# var_9.net
KiCad netlist of a schematic drawn in Altium Designer
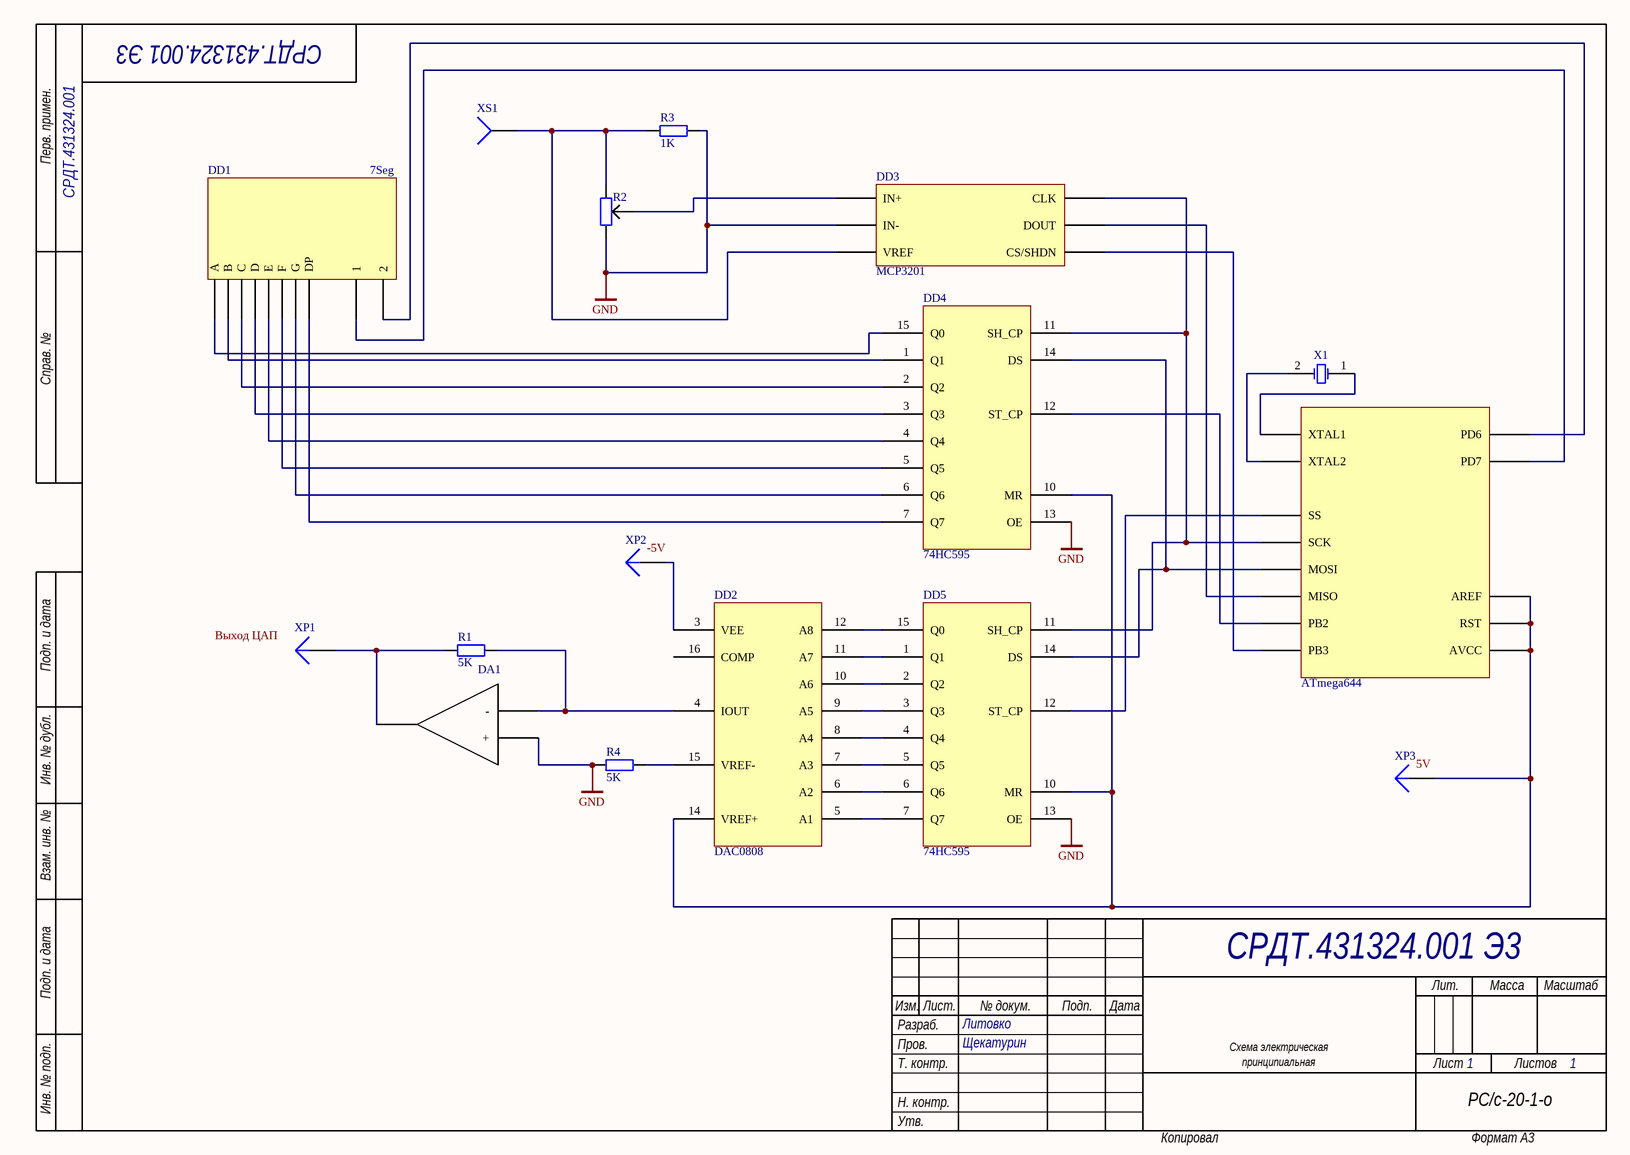
[diagram p0: var 9.SchDoc]

(export (version "E")
  (design (tool "Eeschema 10.0.6"))
  (components
    (comp (ref "*") (value "Potentiometr") (libsource (lib "lib") (part "Potentiometr")))
    (comp (ref "ATmega644") (value "mcu") (libsource (lib "lib") (part "mcu")))
    (comp (ref "DA1") (value "OP1P") (libsource (lib "lib") (part "OP1P")))
    (comp (ref "DD1") (value "7Seg") (libsource (lib "lib") (part "7Seg")))
    (comp (ref "DD2") (value "DAC0808") (libsource (lib "lib") (part "DAC0808")))
    (comp (ref "DD3") (value "MCP3201") (libsource (lib "lib") (part "MCP3201")))
    (comp (ref "DD4") (value "74HC595") (libsource (lib "lib") (part "74HC595")))
    (comp (ref "DD5") (value "74HC595") (libsource (lib "lib") (part "74HC595")))
    (comp (ref "R1")
      (value "5K")
      (footprint "AXIAL-0.4")
      (description "Resistor")
      (fields (field (name "Comment") "Res2") (field (name "PUBLISHER") "Altium Limited"))
      (libsource (lib "") (part "Res2_1"))
    )
    (comp (ref "R2")
      (value "Res2")
      (footprint "AXIAL-0.4")
      (description "Resistor")
      (fields (field (name "PUBLISHER") "Altium Limited"))
      (libsource (lib "Miscellaneous Devices") (part "Res2"))
    )
    (comp (ref "R3")
      (value "1K")
      (footprint "AXIAL-0.4")
      (description "Resistor")
      (fields (field (name "Comment") "Res2") (field (name "PUBLISHER") "Altium Limited"))
      (libsource (lib "") (part "Res2_1"))
    )
    (comp (ref "R4")
      (value "5K")
      (footprint "AXIAL-0.4")
      (description "Resistor")
      (fields (field (name "Comment") "Res2") (field (name "PUBLISHER") "Altium Limited"))
      (libsource (lib "") (part "Res2_1"))
    )
    (comp (ref "X1")
      (value "XTAL")
      (footprint "R38")
      (description "Crystal Oscillator")
      (fields (field (name "PUBLISHER") "Altium Limited"))
      (libsource (lib "Miscellaneous Devices") (part "XTAL"))
    )
    (comp (ref "XP1")
      (value "Plug")
      (footprint "PIN1")
      (fields (field (name "PUBLISHER") "Altium Limited"))
      (libsource (lib "Miscellaneous Connectors") (part "Plug"))
    )
    (comp (ref "XP2")
      (value "Plug")
      (footprint "PIN1")
      (fields (field (name "PUBLISHER") "Altium Limited"))
      (libsource (lib "Miscellaneous Connectors") (part "Plug"))
    )
    (comp (ref "XP3")
      (value "Plug")
      (footprint "PIN1")
      (fields (field (name "PUBLISHER") "Altium Limited"))
      (libsource (lib "Miscellaneous Connectors") (part "Plug"))
    )
    (comp (ref "XS1")
      (value "Socket")
      (footprint "PIN1")
      (fields (field (name "PUBLISHER") "Altium Limited"))
      (libsource (lib "Miscellaneous Connectors") (part "Socket"))
    )
  )
  (nets
    (net (code "4") (name "GND") (class "Default")
      (node (ref "DA1") (pin "33") (pinfunction "+_33") (pintype "passive"))
      (node (ref "DD3") (pin "3") (pinfunction "IN-_3") (pintype "passive"))
      (node (ref "DD4") (pin "13") (pinfunction "OE_13") (pintype "passive"))
      (node (ref "DD5") (pin "13") (pinfunction "OE_13") (pintype "passive"))
      (node (ref "R2") (pin "1") (pinfunction "1_1") (pintype "passive"))
      (node (ref "R3") (pin "2") (pinfunction "2_2") (pintype "passive"))
      (node (ref "R4") (pin "1") (pinfunction "1_1") (pintype "passive"))
    )
    (net (code "5") (name "Net-(ATmega644-AREF)") (class "Default")
      (node (ref "ATmega644") (pin "15") (pinfunction "AREF_15") (pintype "passive"))
      (node (ref "ATmega644") (pin "16") (pinfunction "AVCC_16") (pintype "passive"))
      (node (ref "ATmega644") (pin "RST") (pinfunction "RST_RST") (pintype "passive"))
      (node (ref "DD2") (pin "14") (pinfunction "VREF+_14") (pintype "passive"))
      (node (ref "DD4") (pin "10") (pinfunction "MR_10") (pintype "passive"))
      (node (ref "DD5") (pin "10") (pinfunction "MR_10") (pintype "passive"))
      (node (ref "XP3") (pin "1") (pinfunction "1_1") (pintype "passive"))
    )
    (net (code "6") (name "Net-(ATmega644-MISO)") (class "Default")
      (node (ref "ATmega644") (pin "5") (pinfunction "MISO_5") (pintype "passive"))
      (node (ref "DD3") (pin "RST") (pinfunction "DOUT_RST") (pintype "passive"))
    )
    (net (code "7") (name "Net-(ATmega644-MOSI)") (class "Default")
      (node (ref "ATmega644") (pin "4") (pinfunction "MOSI_4") (pintype "passive"))
      (node (ref "DD4") (pin "14") (pinfunction "DS_14") (pintype "passive"))
      (node (ref "DD5") (pin "14") (pinfunction "DS_14") (pintype "passive"))
    )
    (net (code "8") (name "Net-(ATmega644-PB2)") (class "Default")
      (node (ref "ATmega644") (pin "6") (pinfunction "PB2_6") (pintype "passive"))
      (node (ref "DD4") (pin "12") (pinfunction "ST_CP_12") (pintype "passive"))
    )
    (net (code "9") (name "Net-(ATmega644-PB3)") (class "Default")
      (node (ref "ATmega644") (pin "7") (pinfunction "PB3_7") (pintype "passive"))
      (node (ref "DD3") (pin "16") (pinfunction "CS/SHDN_16") (pintype "passive"))
    )
    (net (code "10") (name "Net-(ATmega644-PD6)") (class "Default")
      (node (ref "ATmega644") (pin "8") (pinfunction "PD6_8") (pintype "passive"))
      (node (ref "DD1") (pin "44") (pinfunction "2_44") (pintype "passive"))
    )
    (net (code "11") (name "Net-(ATmega644-PD7)") (class "Default")
      (node (ref "ATmega644") (pin "9") (pinfunction "PD7_9") (pintype "passive"))
      (node (ref "DD1") (pin "43") (pinfunction "1_43") (pintype "passive"))
    )
    (net (code "12") (name "Net-(ATmega644-SCK)") (class "Default")
      (node (ref "ATmega644") (pin "3") (pinfunction "SCK_3") (pintype "passive"))
      (node (ref "DD3") (pin "15") (pinfunction "CLK_15") (pintype "passive"))
      (node (ref "DD4") (pin "11") (pinfunction "SH_CP_11") (pintype "passive"))
      (node (ref "DD5") (pin "11") (pinfunction "SH_CP_11") (pintype "passive"))
    )
    (net (code "13") (name "Net-(ATmega644-SS)") (class "Default")
      (node (ref "ATmega644") (pin "2") (pinfunction "SS_2") (pintype "passive"))
      (node (ref "DD5") (pin "12") (pinfunction "ST_CP_12") (pintype "passive"))
    )
    (net (code "14") (name "Net-(ATmega644-XTAL2)") (class "Default")
      (node (ref "ATmega644") (pin "17") (pinfunction "XTAL2_17") (pintype "passive"))
      (node (ref "X1") (pin "2") (pinfunction "OSC2_2") (pintype "passive"))
    )
    (net (code "15") (name "Net-(DA1--)") (class "Default")
      (node (ref "DA1") (pin "32") (pinfunction "-_32") (pintype "passive"))
      (node (ref "DD2") (pin "4") (pinfunction "IOUT_4") (pintype "passive"))
      (node (ref "R1") (pin "2") (pinfunction "2_2") (pintype "passive"))
    )
    (net (code "16") (name "Net-(DA1-Pad31)") (class "Default")
      (node (ref "DA1") (pin "31") (pinfunction "31_31") (pintype "passive"))
      (node (ref "R1") (pin "1") (pinfunction "1_1") (pintype "passive"))
      (node (ref "XP1") (pin "1") (pinfunction "1_1") (pintype "passive"))
    )
    (net (code "17") (name "Net-(DD1-A)") (class "Default")
      (node (ref "DD1") (pin "35") (pinfunction "A_35") (pintype "passive"))
      (node (ref "DD4") (pin "15") (pinfunction "Q0_15") (pintype "passive"))
    )
    (net (code "18") (name "Net-(DD1-B)") (class "Default")
      (node (ref "DD1") (pin "36") (pinfunction "B_36") (pintype "passive"))
      (node (ref "DD4") (pin "1") (pinfunction "Q1_1") (pintype "passive"))
    )
    (net (code "19") (name "Net-(DD1-C)") (class "Default")
      (node (ref "DD1") (pin "37") (pinfunction "C_37") (pintype "passive"))
      (node (ref "DD4") (pin "2") (pinfunction "Q2_2") (pintype "passive"))
    )
    (net (code "20") (name "Net-(DD1-D)") (class "Default")
      (node (ref "DD1") (pin "38") (pinfunction "D_38") (pintype "passive"))
      (node (ref "DD4") (pin "3") (pinfunction "Q3_3") (pintype "passive"))
    )
    (net (code "21") (name "Net-(DD1-DP)") (class "Default")
      (node (ref "DD1") (pin "42") (pinfunction "DP_42") (pintype "passive"))
      (node (ref "DD4") (pin "7") (pinfunction "Q7_7") (pintype "passive"))
    )
    (net (code "22") (name "Net-(DD1-E)") (class "Default")
      (node (ref "DD1") (pin "39") (pinfunction "E_39") (pintype "passive"))
      (node (ref "DD4") (pin "4") (pinfunction "Q4_4") (pintype "passive"))
    )
    (net (code "23") (name "Net-(DD1-F)") (class "Default")
      (node (ref "DD1") (pin "40") (pinfunction "F_40") (pintype "passive"))
      (node (ref "DD4") (pin "5") (pinfunction "Q5_5") (pintype "passive"))
    )
    (net (code "24") (name "Net-(DD1-G)") (class "Default")
      (node (ref "DD1") (pin "41") (pinfunction "G_41") (pintype "passive"))
      (node (ref "DD4") (pin "6") (pinfunction "Q6_6") (pintype "passive"))
    )
    (net (code "25") (name "Net-(DD2-A1)") (class "Default")
      (node (ref "DD2") (pin "5") (pinfunction "A1_5") (pintype "passive"))
      (node (ref "DD5") (pin "7") (pinfunction "Q7_7") (pintype "passive"))
    )
    (net (code "26") (name "Net-(DD2-A2)") (class "Default")
      (node (ref "DD2") (pin "6") (pinfunction "A2_6") (pintype "passive"))
      (node (ref "DD5") (pin "6") (pinfunction "Q6_6") (pintype "passive"))
    )
    (net (code "27") (name "Net-(DD2-A3)") (class "Default")
      (node (ref "DD2") (pin "7") (pinfunction "A3_7") (pintype "passive"))
      (node (ref "DD5") (pin "5") (pinfunction "Q5_5") (pintype "passive"))
    )
    (net (code "28") (name "Net-(DD2-A4)") (class "Default")
      (node (ref "DD2") (pin "8") (pinfunction "A4_8") (pintype "passive"))
      (node (ref "DD5") (pin "4") (pinfunction "Q4_4") (pintype "passive"))
    )
    (net (code "29") (name "Net-(DD2-A5)") (class "Default")
      (node (ref "DD2") (pin "9") (pinfunction "A5_9") (pintype "passive"))
      (node (ref "DD5") (pin "3") (pinfunction "Q3_3") (pintype "passive"))
    )
    (net (code "30") (name "Net-(DD2-A6)") (class "Default")
      (node (ref "DD2") (pin "10") (pinfunction "A6_10") (pintype "passive"))
      (node (ref "DD5") (pin "2") (pinfunction "Q2_2") (pintype "passive"))
    )
    (net (code "31") (name "Net-(DD2-A7)") (class "Default")
      (node (ref "DD2") (pin "11") (pinfunction "A7_11") (pintype "passive"))
      (node (ref "DD5") (pin "1") (pinfunction "Q1_1") (pintype "passive"))
    )
    (net (code "32") (name "Net-(DD2-A8)") (class "Default")
      (node (ref "DD2") (pin "12") (pinfunction "A8_12") (pintype "passive"))
      (node (ref "DD5") (pin "15") (pinfunction "Q0_15") (pintype "passive"))
    )
    (net (code "33") (name "Net-(DD2-VEE)") (class "Default")
      (node (ref "DD2") (pin "3") (pinfunction "VEE_3") (pintype "passive"))
      (node (ref "XP2") (pin "1") (pinfunction "1_1") (pintype "passive"))
    )
    (net (code "34") (name "Net-(DD2-VREF-)") (class "Default")
      (node (ref "DD2") (pin "15") (pinfunction "VREF-_15") (pintype "passive"))
      (node (ref "R4") (pin "2") (pinfunction "2_2") (pintype "passive"))
    )
    (net (code "35") (name "Net-(DD3-IN+)") (class "Default")
      (node (ref "*") (pin "34") (pinfunction "34_34") (pintype "passive"))
      (node (ref "DD3") (pin "2") (pinfunction "IN+_2") (pintype "passive"))
    )
    (net (code "36") (name "Net-(DD3-VREF)") (class "Default")
      (node (ref "DD3") (pin "4") (pinfunction "VREF_4") (pintype "passive"))
      (node (ref "R2") (pin "2") (pinfunction "2_2") (pintype "passive"))
      (node (ref "R3") (pin "1") (pinfunction "1_1") (pintype "passive"))
      (node (ref "XS1") (pin "1") (pinfunction "1_1") (pintype "passive"))
    )
    (net (code "37") (name "Net-(X1-OSC1)") (class "Default")
      (node (ref "ATmega644") (pin "XTAL1") (pinfunction "XTAL1_XTAL1") (pintype "passive"))
      (node (ref "X1") (pin "1") (pinfunction "OSC1_1") (pintype "passive"))
    )
    (net (code "38") (name "unconnected-(DD2-COMP-Pad16)") (class "Default")
      (node (ref "DD2") (pin "16") (pinfunction "COMP_16") (pintype "passive"))
    )
  )
)
